# arduino_dust_density_meter.net
KiCad netlist of a schematic drawn in EAGLE
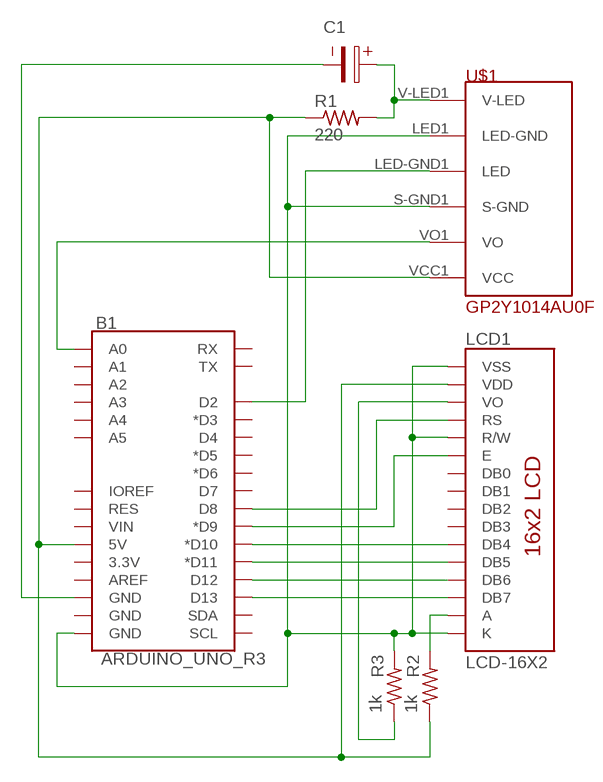
[diagram p0: schematic, sheet 1]

(export (version "E")
  (design (tool "Eeschema 10.0.6"))
  (components
    (comp (ref "B1")
      (value "ARDUINO_UNO_R3")
      (footprint "eagle-import:UNO_R3_SHIELD")
      (libsource (lib "eagle-import") (part "ARDUINO_UNO_R3_SHIELDBASIC"))
    )
    (comp (ref "C1")
      (value "WCAP-PTG5_10X12,5_870025575007")
      (footprint "eagle-import:10X5X0.9(DXAXB)")
      (libsource (lib "eagle-import") (part "WCAP-PTG5_870025575007_10X12,5"))
    )
    (comp (ref "LCD1")
      (value "LCD-16X2")
      (footprint "eagle-import:LCD-16X2_NOHOLESNOSILK")
      (libsource (lib "eagle-import") (part "LCD-16X2NOHOLES"))
    )
    (comp (ref "R1")
      (value "220")
      (footprint "eagle-import:0309_12")
      (libsource (lib "eagle-import") (part "R-US_0309/12"))
    )
    (comp (ref "R2")
      (value "1k")
      (footprint "eagle-import:0309_12")
      (libsource (lib "eagle-import") (part "R-US_0309/12"))
    )
    (comp (ref "R3")
      (value "1k")
      (footprint "eagle-import:0309_12")
      (libsource (lib "eagle-import") (part "R-US_0309/12"))
    )
    (comp (ref "U$1")
      (value "GP2Y1014AU0F")
      (footprint "eagle-import:GP2Y1014AU0F")
      (libsource (lib "eagle-import") (part "GP2Y1014AU0F"))
    )
  )
  (nets
    (net (code "1") (name "Net-(B1-*D9)") (class "Default")
      (node (ref "B1") (pin "D9") (pinfunction "*D9_D9") (pintype "bidirectional"))
      (node (ref "LCD1") (pin "6") (pinfunction "E_6") (pintype "input"))
    )
    (net (code "2") (name "Net-(B1-*D10)") (class "Default")
      (node (ref "B1") (pin "D10") (pinfunction "*D10_D10") (pintype "bidirectional"))
      (node (ref "LCD1") (pin "11") (pinfunction "DB4_11") (pintype "bidirectional"))
    )
    (net (code "3") (name "Net-(B1-*D11)") (class "Default")
      (node (ref "B1") (pin "D11") (pinfunction "*D11_D11") (pintype "bidirectional"))
      (node (ref "LCD1") (pin "12") (pinfunction "DB5_12") (pintype "bidirectional"))
    )
    (net (code "4") (name "Net-(B1-GND-PadGND@2)") (class "Default")
      (node (ref "B1") (pin "GND@2") (pinfunction "GND_GND@2") (pintype "bidirectional"))
      (node (ref "C1") (pin "2") (pinfunction "2_2") (pintype "passive"))
    )
    (net (code "5") (name "Net-(LCD1-A)") (class "Default")
      (node (ref "LCD1") (pin "15") (pinfunction "A_15") (pintype "power_in"))
      (node (ref "R2") (pin "2") (pinfunction "2_2") (pintype "passive"))
    )
    (net (code "6") (name "Net-(LCD1-DB6)") (class "Default")
      (node (ref "B1") (pin "D12") (pinfunction "D12_D12") (pintype "bidirectional"))
      (node (ref "LCD1") (pin "13") (pinfunction "DB6_13") (pintype "bidirectional"))
    )
    (net (code "7") (name "Net-(LCD1-DB7)") (class "Default")
      (node (ref "B1") (pin "D13") (pinfunction "D13_D13") (pintype "bidirectional"))
      (node (ref "LCD1") (pin "14") (pinfunction "DB7_14") (pintype "bidirectional"))
    )
    (net (code "8") (name "Net-(LCD1-K)") (class "Default")
      (node (ref "B1") (pin "GND@0") (pinfunction "GND_GND@0") (pintype "bidirectional"))
      (node (ref "LCD1") (pin "1") (pinfunction "VSS_1") (pintype "power_in"))
      (node (ref "LCD1") (pin "16") (pinfunction "K_16") (pintype "power_in"))
      (node (ref "LCD1") (pin "5") (pinfunction "R/W_5") (pintype "input"))
      (node (ref "R3") (pin "2") (pinfunction "2_2") (pintype "passive"))
      (node (ref "U$1") (pin "LED1") (pinfunction "LED-GND_LED1") (pintype "bidirectional"))
      (node (ref "U$1") (pin "S-GND1") (pinfunction "S-GND_S-GND1") (pintype "bidirectional"))
    )
    (net (code "9") (name "Net-(LCD1-RS)") (class "Default")
      (node (ref "B1") (pin "D8") (pinfunction "D8_D8") (pintype "bidirectional"))
      (node (ref "LCD1") (pin "4") (pinfunction "RS_4") (pintype "input"))
    )
    (net (code "10") (name "Net-(LCD1-VDD)") (class "Default")
      (node (ref "B1") (pin "5V") (pinfunction "5V_5V") (pintype "bidirectional"))
      (node (ref "LCD1") (pin "2") (pinfunction "VDD_2") (pintype "power_in"))
      (node (ref "R1") (pin "1") (pinfunction "1_1") (pintype "passive"))
      (node (ref "R2") (pin "1") (pinfunction "1_1") (pintype "passive"))
      (node (ref "U$1") (pin "VCC1") (pinfunction "VCC_VCC1") (pintype "bidirectional"))
    )
    (net (code "11") (name "Net-(LCD1-VO)") (class "Default")
      (node (ref "LCD1") (pin "3") (pinfunction "VO_3") (pintype "bidirectional"))
      (node (ref "R3") (pin "1") (pinfunction "1_1") (pintype "passive"))
    )
    (net (code "12") (name "Net-(U$1-LED)") (class "Default")
      (node (ref "B1") (pin "D2") (pinfunction "D2_D2") (pintype "bidirectional"))
      (node (ref "U$1") (pin "LED-GND1") (pinfunction "LED_LED-GND1") (pintype "bidirectional"))
    )
    (net (code "13") (name "Net-(U$1-V-LED)") (class "Default")
      (node (ref "C1") (pin "1") (pinfunction "1_1") (pintype "passive"))
      (node (ref "R1") (pin "2") (pinfunction "2_2") (pintype "passive"))
      (node (ref "U$1") (pin "V-LED1") (pinfunction "V-LED_V-LED1") (pintype "bidirectional"))
    )
    (net (code "14") (name "Net-(U$1-VO)") (class "Default")
      (node (ref "B1") (pin "A0") (pinfunction "A0_A0") (pintype "bidirectional"))
      (node (ref "U$1") (pin "VO1") (pinfunction "VO_VO1") (pintype "bidirectional"))
    )
    (net (code "15") (name "unconnected-(B1-*D3-PadD3)") (class "Default")
      (node (ref "B1") (pin "D3") (pinfunction "*D3_D3") (pintype "bidirectional"))
    )
    (net (code "16") (name "unconnected-(B1-*D5-PadD5)") (class "Default")
      (node (ref "B1") (pin "D5") (pinfunction "*D5_D5") (pintype "bidirectional"))
    )
    (net (code "17") (name "unconnected-(B1-*D6-PadD6)") (class "Default")
      (node (ref "B1") (pin "D6") (pinfunction "*D6_D6") (pintype "bidirectional"))
    )
    (net (code "18") (name "unconnected-(B1-GND-PadGND@1)") (class "Default")
      (node (ref "B1") (pin "GND@1") (pinfunction "GND_GND@1") (pintype "bidirectional"))
    )
    (net (code "19") (name "unconnected-(B1-Pad3.3V)") (class "Default")
      (node (ref "B1") (pin "3.3V") (pinfunction "3.3V_3.3V") (pintype "bidirectional"))
    )
    (net (code "20") (name "unconnected-(B1-PadA1)") (class "Default")
      (node (ref "B1") (pin "A1") (pinfunction "A1_A1") (pintype "bidirectional"))
    )
    (net (code "21") (name "unconnected-(B1-PadA2)") (class "Default")
      (node (ref "B1") (pin "A2") (pinfunction "A2_A2") (pintype "bidirectional"))
    )
    (net (code "22") (name "unconnected-(B1-PadA3)") (class "Default")
      (node (ref "B1") (pin "A3") (pinfunction "A3_A3") (pintype "bidirectional"))
    )
    (net (code "23") (name "unconnected-(B1-PadA4)") (class "Default")
      (node (ref "B1") (pin "A4") (pinfunction "A4_A4") (pintype "bidirectional"))
    )
    (net (code "24") (name "unconnected-(B1-PadA5)") (class "Default")
      (node (ref "B1") (pin "A5") (pinfunction "A5_A5") (pintype "bidirectional"))
    )
    (net (code "25") (name "unconnected-(B1-PadAREF)") (class "Default")
      (node (ref "B1") (pin "AREF") (pinfunction "AREF_AREF") (pintype "bidirectional"))
    )
    (net (code "26") (name "unconnected-(B1-PadD4)") (class "Default")
      (node (ref "B1") (pin "D4") (pinfunction "D4_D4") (pintype "bidirectional"))
    )
    (net (code "27") (name "unconnected-(B1-PadD7)") (class "Default")
      (node (ref "B1") (pin "D7") (pinfunction "D7_D7") (pintype "bidirectional"))
    )
    (net (code "28") (name "unconnected-(B1-PadIOREF)") (class "Default")
      (node (ref "B1") (pin "IOREF") (pinfunction "IOREF_IOREF") (pintype "bidirectional"))
    )
    (net (code "29") (name "unconnected-(B1-PadRES)") (class "Default")
      (node (ref "B1") (pin "RES") (pinfunction "RES_RES") (pintype "bidirectional"))
    )
    (net (code "30") (name "unconnected-(B1-PadRX)") (class "Default")
      (node (ref "B1") (pin "RX") (pinfunction "RX_RX") (pintype "bidirectional"))
    )
    (net (code "31") (name "unconnected-(B1-PadSCL)") (class "Default")
      (node (ref "B1") (pin "SCL") (pinfunction "SCL_SCL") (pintype "bidirectional"))
    )
    (net (code "32") (name "unconnected-(B1-PadSDA)") (class "Default")
      (node (ref "B1") (pin "SDA") (pinfunction "SDA_SDA") (pintype "bidirectional"))
    )
    (net (code "33") (name "unconnected-(B1-PadTX)") (class "Default")
      (node (ref "B1") (pin "TX") (pinfunction "TX_TX") (pintype "bidirectional"))
    )
    (net (code "34") (name "unconnected-(B1-PadVIN)") (class "Default")
      (node (ref "B1") (pin "VIN") (pinfunction "VIN_VIN") (pintype "bidirectional"))
    )
    (net (code "35") (name "unconnected-(LCD1-DB0-Pad7)") (class "Default")
      (node (ref "LCD1") (pin "7") (pinfunction "DB0_7") (pintype "bidirectional"))
    )
    (net (code "36") (name "unconnected-(LCD1-DB1-Pad8)") (class "Default")
      (node (ref "LCD1") (pin "8") (pinfunction "DB1_8") (pintype "bidirectional"))
    )
    (net (code "37") (name "unconnected-(LCD1-DB2-Pad9)") (class "Default")
      (node (ref "LCD1") (pin "9") (pinfunction "DB2_9") (pintype "bidirectional"))
    )
    (net (code "38") (name "unconnected-(LCD1-DB3-Pad10)") (class "Default")
      (node (ref "LCD1") (pin "10") (pinfunction "DB3_10") (pintype "bidirectional"))
    )
  )
)
